# pc_healthypi_move_finger_sensor_v2.net
KiCad netlist of a schematic drawn in EAGLE
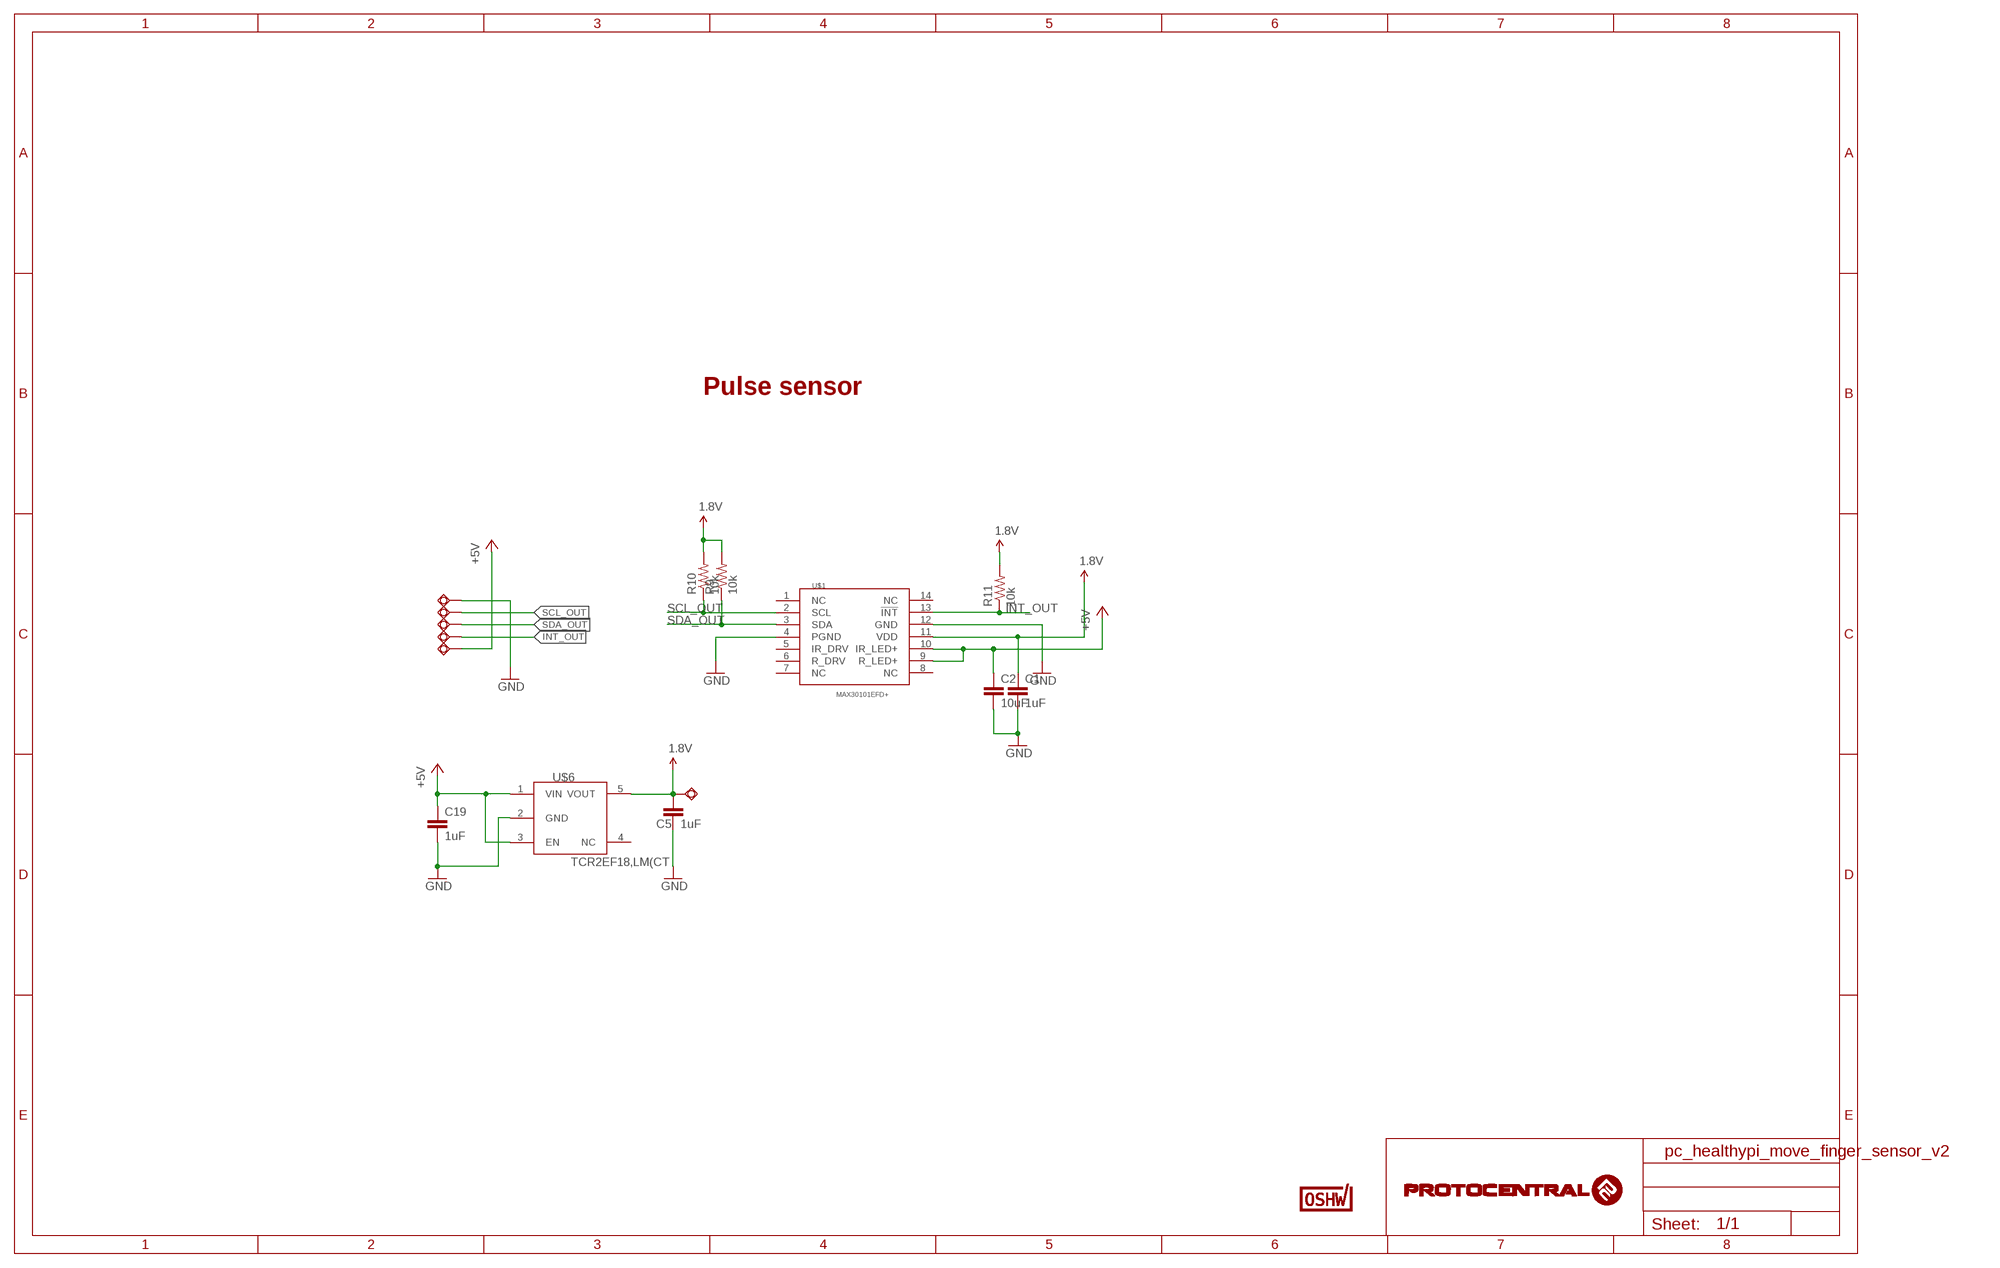
[diagram p0: schematic, sheet 1]

(export (version "E")
  (design (tool "Eeschema 10.0.6"))
  (components
    (comp (ref "C1")
      (value "1uF")
      (footprint "eagle-import:C0402")
      (libsource (lib "eagle-import") (part "C-EUC0402"))
    )
    (comp (ref "C2")
      (value "10uF")
      (footprint "eagle-import:C0402")
      (libsource (lib "eagle-import") (part "C-EUC0402"))
    )
    (comp (ref "C5")
      (value "1uF")
      (footprint "eagle-import:C0402")
      (libsource (lib "eagle-import") (part "C-EUC0402"))
    )
    (comp (ref "C19")
      (value "1uF")
      (footprint "eagle-import:C0402")
      (libsource (lib "eagle-import") (part "C-EUC0402"))
    )
    (comp (ref "R9")
      (value "10k")
      (footprint "eagle-import:R0402")
      (libsource (lib "eagle-import") (part "R-US_R0402"))
    )
    (comp (ref "R10")
      (value "10k")
      (footprint "eagle-import:R0402")
      (libsource (lib "eagle-import") (part "R-US_R0402"))
    )
    (comp (ref "R11")
      (value "10k")
      (footprint "eagle-import:R0402")
      (libsource (lib "eagle-import") (part "R-US_R0402"))
    )
    (comp (ref "SWIO1")
      (value "TPSQTP11R")
      (footprint "eagle-import:TP11R")
      (libsource (lib "eagle-import") (part "TPSQTP11R"))
    )
    (comp (ref "SWIO2")
      (value "TPSQTP11R")
      (footprint "eagle-import:TP11R")
      (libsource (lib "eagle-import") (part "TPSQTP11R"))
    )
    (comp (ref "SWIO3")
      (value "TPSQTP11R")
      (footprint "eagle-import:TP11R")
      (libsource (lib "eagle-import") (part "TPSQTP11R"))
    )
    (comp (ref "SWIO4")
      (value "TPSQTP11R")
      (footprint "eagle-import:TP11R")
      (libsource (lib "eagle-import") (part "TPSQTP11R"))
    )
    (comp (ref "SWIO5")
      (value "TPSQTP11R")
      (footprint "eagle-import:TP11R")
      (libsource (lib "eagle-import") (part "TPSQTP11R"))
    )
    (comp (ref "SWIO6")
      (value "TPSQTP11R")
      (footprint "eagle-import:TP11R")
      (libsource (lib "eagle-import") (part "TPSQTP11R"))
    )
    (comp (ref "U$1")
      (value "MAX30101EFD+")
      (footprint "eagle-import:OESIP-14")
      (libsource (lib "eagle-import") (part "MAX30100"))
    )
    (comp (ref "U$6")
      (value "TCR2EF18,LM(CT")
      (footprint "eagle-import:SOT95P285X140-5N")
      (libsource (lib "eagle-import") (part "AP7354D-18W5-7"))
    )
    (comp (ref "U$9")
      (value "CERT-SMALL")
      (footprint "eagle-import:CERT-SMALL-SILK")
      (libsource (lib "eagle-import") (part "CERT-SMALL"))
    )
  )
  (nets
    (net (code "1") (name "+5V") (class "Default")
      (node (ref "C19") (pin "1") (pinfunction "1_1") (pintype "passive"))
      (node (ref "C2") (pin "1") (pinfunction "1_1") (pintype "passive"))
      (node (ref "SWIO4") (pin "TP") (pinfunction "TP_TP") (pintype "input"))
      (node (ref "U$1") (pin "10") (pinfunction "IR_LED+_10") (pintype "bidirectional"))
      (node (ref "U$1") (pin "9") (pinfunction "R_LED+_9") (pintype "bidirectional"))
      (node (ref "U$6") (pin "1") (pinfunction "VIN_1") (pintype "bidirectional"))
      (node (ref "U$6") (pin "3") (pinfunction "EN_3") (pintype "bidirectional"))
    )
    (net (code "2") (name "1.8V") (class "Default")
      (node (ref "C1") (pin "1") (pinfunction "1_1") (pintype "passive"))
      (node (ref "C5") (pin "1") (pinfunction "1_1") (pintype "passive"))
      (node (ref "R10") (pin "2") (pinfunction "2_2") (pintype "passive"))
      (node (ref "R11") (pin "2") (pinfunction "2_2") (pintype "passive"))
      (node (ref "R9") (pin "2") (pinfunction "2_2") (pintype "passive"))
      (node (ref "SWIO5") (pin "TP") (pinfunction "TP_TP") (pintype "input"))
      (node (ref "U$1") (pin "11") (pinfunction "VDD_11") (pintype "bidirectional"))
      (node (ref "U$6") (pin "5") (pinfunction "VOUT_5") (pintype "bidirectional"))
    )
    (net (code "3") (name "GND") (class "Default")
      (node (ref "C1") (pin "2") (pinfunction "2_2") (pintype "passive"))
      (node (ref "C19") (pin "2") (pinfunction "2_2") (pintype "passive"))
      (node (ref "C2") (pin "2") (pinfunction "2_2") (pintype "passive"))
      (node (ref "C5") (pin "2") (pinfunction "2_2") (pintype "passive"))
      (node (ref "SWIO6") (pin "TP") (pinfunction "TP_TP") (pintype "input"))
      (node (ref "U$1") (pin "12") (pinfunction "GND_12") (pintype "bidirectional"))
      (node (ref "U$1") (pin "4") (pinfunction "PGND_4") (pintype "bidirectional"))
      (node (ref "U$6") (pin "2") (pinfunction "GND_2") (pintype "bidirectional"))
    )
    (net (code "4") (name "INT_OUT") (class "Default")
      (node (ref "R11") (pin "1") (pinfunction "1_1") (pintype "passive"))
      (node (ref "SWIO3") (pin "TP") (pinfunction "TP_TP") (pintype "input"))
      (node (ref "U$1") (pin "13") (pinfunction "~{INT}_13") (pintype "bidirectional"))
    )
    (net (code "5") (name "SCL_OUT") (class "Default")
      (node (ref "R10") (pin "1") (pinfunction "1_1") (pintype "passive"))
      (node (ref "SWIO1") (pin "TP") (pinfunction "TP_TP") (pintype "input"))
      (node (ref "U$1") (pin "2") (pinfunction "SCL_2") (pintype "bidirectional"))
    )
    (net (code "6") (name "SDA_OUT") (class "Default")
      (node (ref "R9") (pin "1") (pinfunction "1_1") (pintype "passive"))
      (node (ref "SWIO2") (pin "TP") (pinfunction "TP_TP") (pintype "input"))
      (node (ref "U$1") (pin "3") (pinfunction "SDA_3") (pintype "bidirectional"))
    )
    (net (code "7") (name "unconnected-(U$1-IR_DRV-Pad5)") (class "Default")
      (node (ref "U$1") (pin "5") (pinfunction "IR_DRV_5") (pintype "bidirectional"))
    )
    (net (code "8") (name "unconnected-(U$1-NC-Pad1)") (class "Default")
      (node (ref "U$1") (pin "1") (pinfunction "NC_1") (pintype "bidirectional"))
    )
    (net (code "9") (name "unconnected-(U$1-NC-Pad7)") (class "Default")
      (node (ref "U$1") (pin "7") (pinfunction "NC_7") (pintype "bidirectional"))
    )
    (net (code "10") (name "unconnected-(U$1-NC-Pad8)") (class "Default")
      (node (ref "U$1") (pin "8") (pinfunction "NC_8") (pintype "bidirectional"))
    )
    (net (code "11") (name "unconnected-(U$1-NC-Pad14)") (class "Default")
      (node (ref "U$1") (pin "14") (pinfunction "NC_14") (pintype "bidirectional"))
    )
    (net (code "12") (name "unconnected-(U$1-R_DRV-Pad6)") (class "Default")
      (node (ref "U$1") (pin "6") (pinfunction "R_DRV_6") (pintype "bidirectional"))
    )
    (net (code "13") (name "unconnected-(U$6-NC-Pad4)") (class "Default")
      (node (ref "U$6") (pin "4") (pinfunction "NC_4") (pintype "bidirectional"))
    )
  )
)
